# 1-Schematic_NRF24L01P-R.net
KiCad netlist of a schematic drawn in EasyEDA
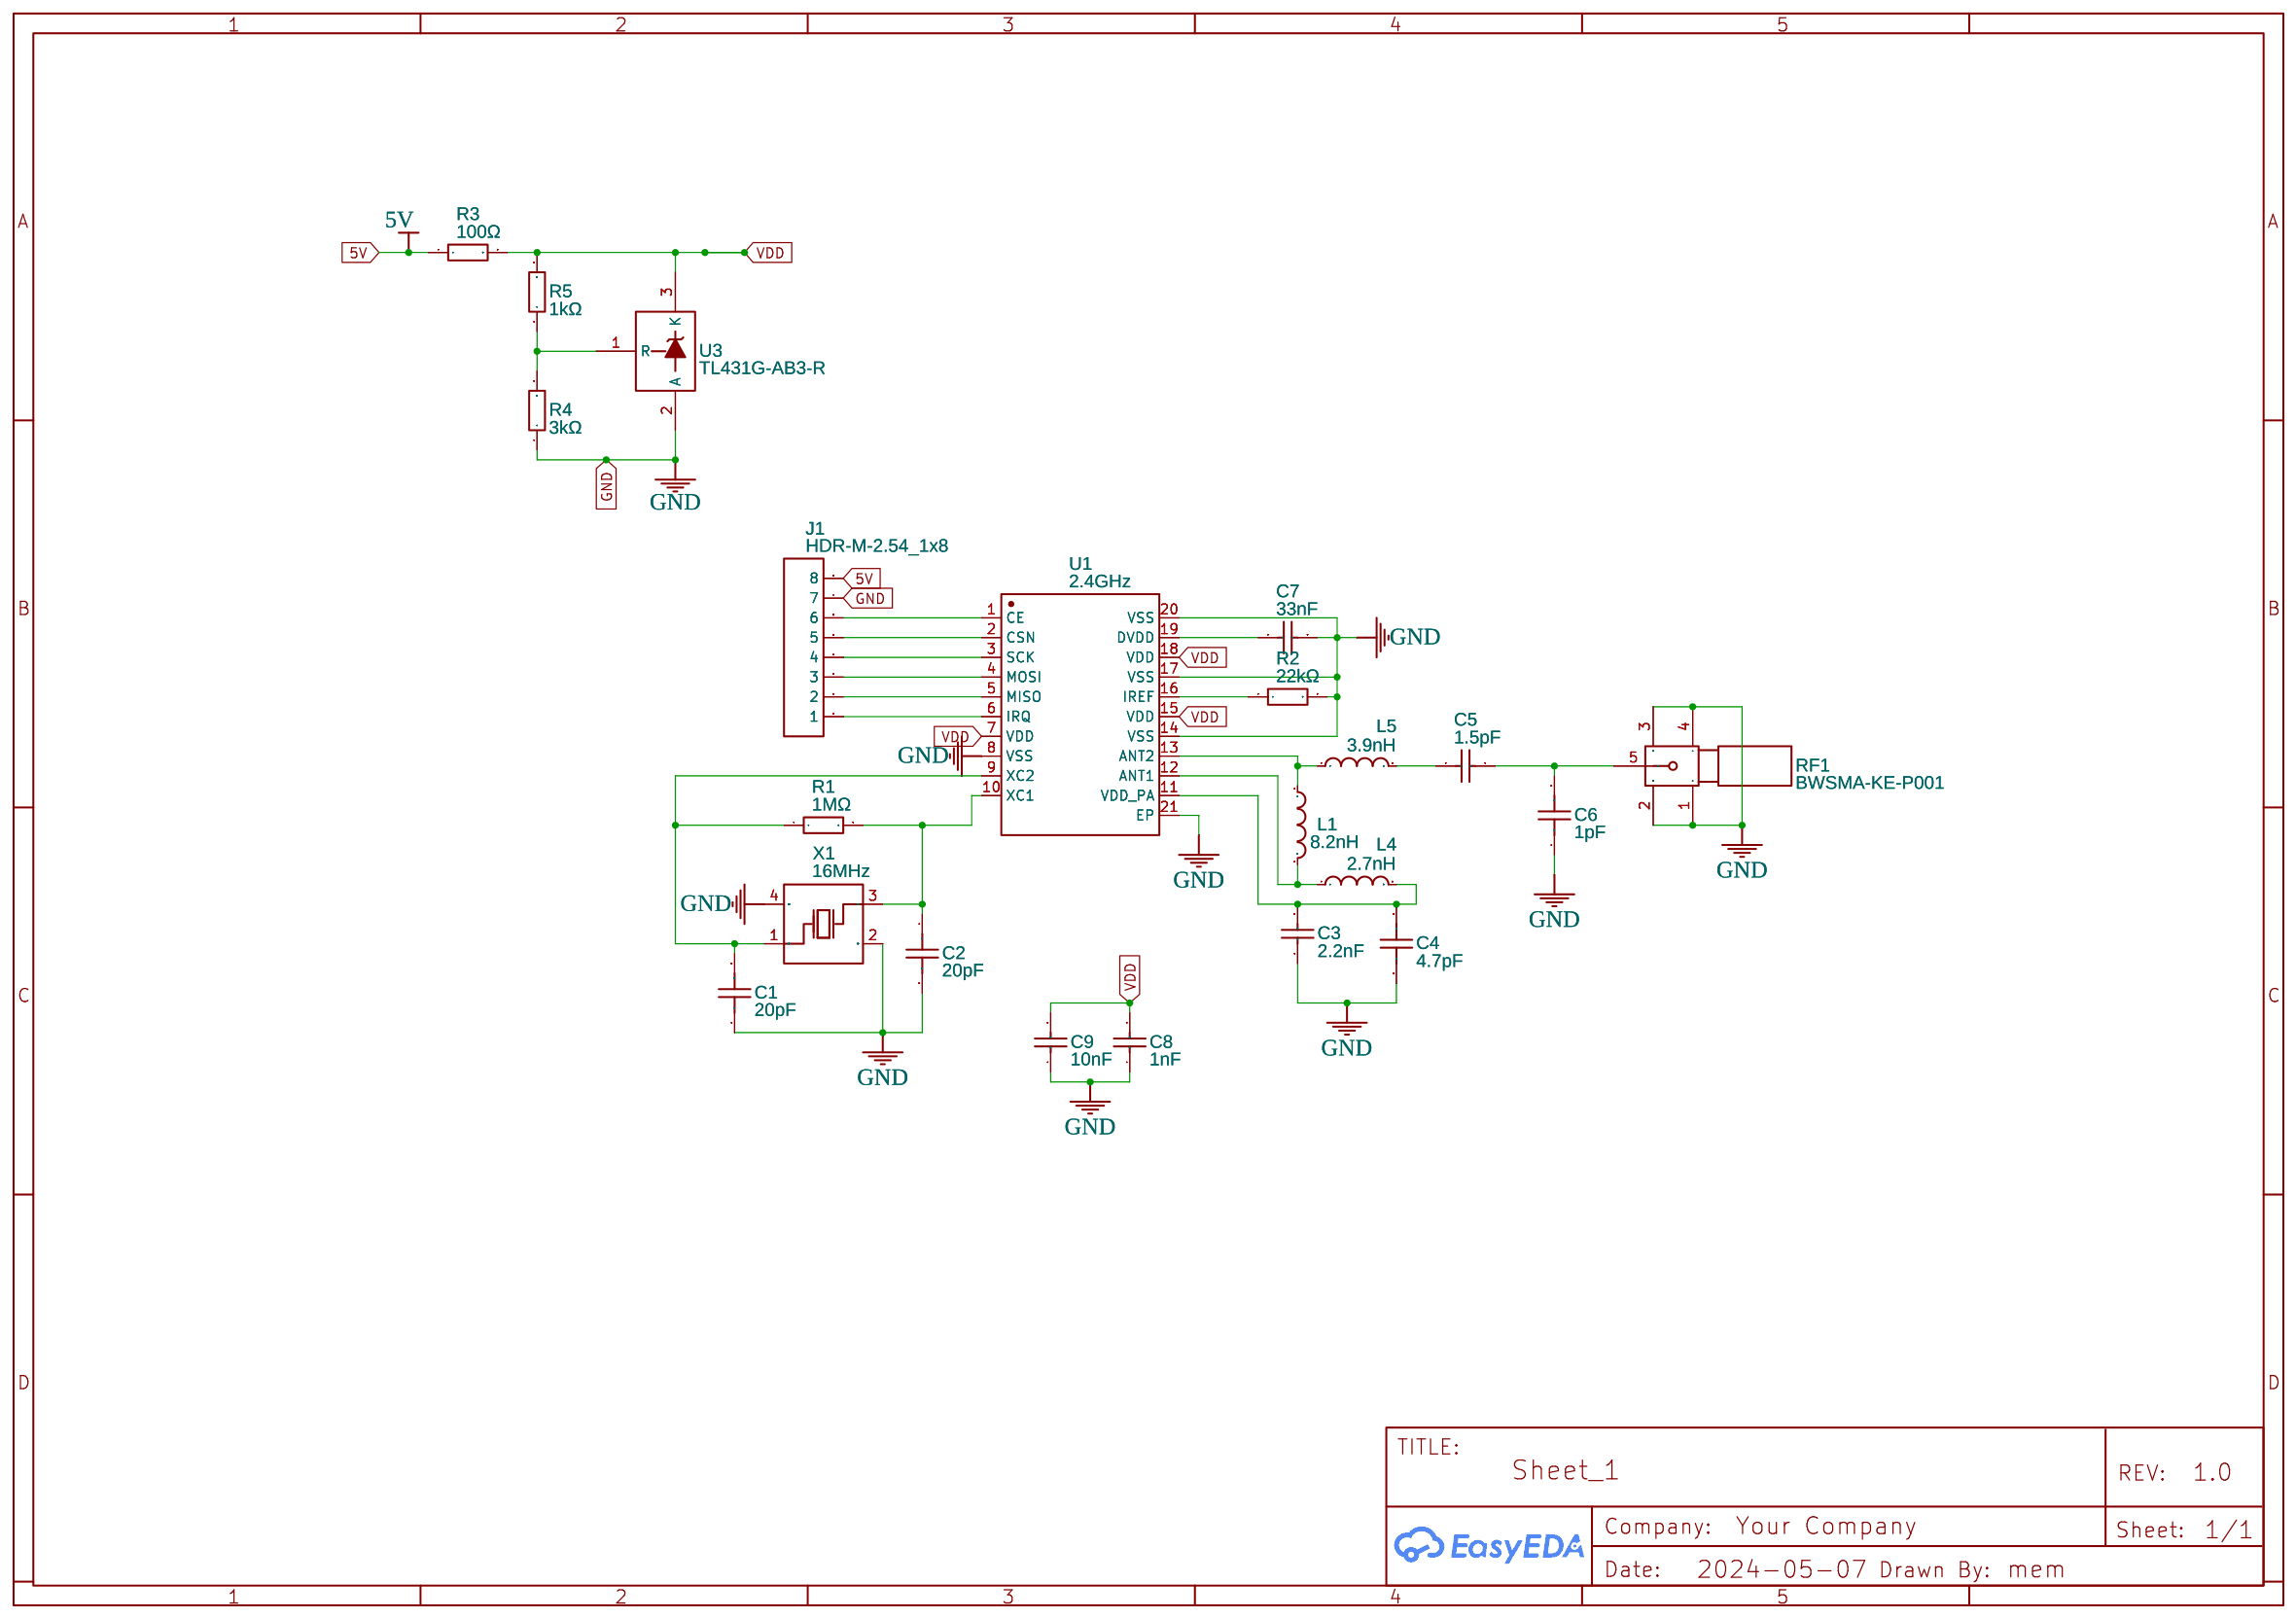
[diagram p0: schematic sheet]

(export (version "E")
  (design (tool "Eeschema 10.0.6"))
  (components
    (comp (ref "C1")
      (value "20pF")
      (fields
        (field (name "Manufacturer Part") "CC0805GRNPO9BN200")
        (field (name "Manufacturer") "YAGEO(国巨)")
      )
      (libsource (lib "") (part "CC0805GRNPO9BN200_1"))
    )
    (comp (ref "C2")
      (value "20pF")
      (fields
        (field (name "Manufacturer Part") "CC0805GRNPO9BN200")
        (field (name "Manufacturer") "YAGEO(国巨)")
      )
      (libsource (lib "") (part "CC0805GRNPO9BN200"))
    )
    (comp (ref "C3")
      (value "2.2nF")
      (fields (field (name "Manufacturer Part") "0805B222K500NT") (field (name "Manufacturer") "FH(风华)"))
      (libsource (lib "") (part "0805B222K500NT"))
    )
    (comp (ref "C4")
      (value "4.7pF")
      (fields
        (field (name "Manufacturer Part") "CC0805BRNPO9BN4R7")
        (field (name "Manufacturer") "YAGEO(国巨)")
      )
      (libsource (lib "") (part "CC0805BRNPO9BN4R7"))
    )
    (comp (ref "C5")
      (value "1.5pF")
      (fields (field (name "Manufacturer Part") "0603CG1R5C500NT") (field (name "Manufacturer") "FH(风华)"))
      (libsource (lib "") (part "0603CG1R5C500NT"))
    )
    (comp (ref "C6")
      (value "1pF")
      (fields
        (field (name "Manufacturer Part") "CC0805BRNPO9BN1R0")
        (field (name "Manufacturer") "YAGEO(国巨)")
      )
      (libsource (lib "") (part "CC0805BRNPO9BN1R0"))
    )
    (comp (ref "C7")
      (value "33nF")
      (fields
        (field (name "Manufacturer Part") "CC0805KRX7R9BB333")
        (field (name "Manufacturer") "YAGEO(国巨)")
      )
      (libsource (lib "") (part "CC0805KRX7R9BB333"))
    )
    (comp (ref "C8")
      (value "1nF")
      (fields (field (name "Manufacturer Part") "0805B102K500NT") (field (name "Manufacturer") "FH(风华)"))
      (libsource (lib "") (part "0805B102K500NT"))
    )
    (comp (ref "C9")
      (value "10nF")
      (fields (field (name "Manufacturer Part") "0805B103K500NT") (field (name "Manufacturer") "FH(风华)"))
      (libsource (lib "") (part "0805B103K500NT"))
    )
    (comp (ref "J1") (value "HDR-M-2.54_1x8") (libsource (lib "") (part "HDR-M-2.54_1x8")))
    (comp (ref "L1")
      (value "8.2nH")
      (fields (field (name "Manufacturer Part") "VHF201209H8N2J") (field (name "Manufacturer") "FH(风华)"))
      (libsource (lib "") (part "VHF201209H8N2J"))
    )
    (comp (ref "L4")
      (value "2.7nH")
      (fields
        (field (name "Manufacturer Part") "SCHF201209H2N7ST")
        (field (name "Manufacturer") "Yanchuang(研创)")
      )
      (libsource (lib "") (part "SCHF201209H2N7ST"))
    )
    (comp (ref "L5")
      (value "3.9nH")
      (fields
        (field (name "Manufacturer Part") "SCHF201209H3N9ST")
        (field (name "Manufacturer") "Yanchuang(研创)")
      )
      (libsource (lib "") (part "SCHF201209H3N9ST"))
    )
    (comp (ref "R1")
      (value "1MΩ")
      (fields
        (field (name "Manufacturer Part") "0805W8F1004T5E")
        (field (name "Manufacturer") "UNI-ROYAL(厚声)")
      )
      (libsource (lib "") (part "0805W8F1004T5E"))
    )
    (comp (ref "R2")
      (value "22kΩ")
      (fields
        (field (name "Manufacturer Part") "0805W8F2202T5E")
        (field (name "Manufacturer") "UNI-ROYAL(厚声)")
      )
      (libsource (lib "") (part "0805W8F2202T5E"))
    )
    (comp (ref "R3")
      (value "100Ω")
      (fields
        (field (name "Manufacturer Part") "1206W4F1000T5E")
        (field (name "Manufacturer") "UNI-ROYAL(厚声)")
      )
      (libsource (lib "") (part "1206W4F1000T5E"))
    )
    (comp (ref "R4")
      (value "3kΩ")
      (fields
        (field (name "Manufacturer Part") "1206W4F3001T5E")
        (field (name "Manufacturer") "UNI-ROYAL(厚声)")
      )
      (libsource (lib "") (part "1206W4F3001T5E"))
    )
    (comp (ref "R5")
      (value "1kΩ")
      (fields
        (field (name "Manufacturer Part") "1206W4F1001T5E")
        (field (name "Manufacturer") "UNI-ROYAL(厚声)")
      )
      (libsource (lib "") (part "1206W4F1001T5E"))
    )
    (comp (ref "RF1")
      (value "BWSMA-KE-P001")
      (fields (field (name "Manufacturer") "BAT WIRELESS(蝙蝠无线)"))
      (libsource (lib "") (part "BWSMA-KE-P001"))
    )
    (comp (ref "U1")
      (value "2.4GHz")
      (fields (field (name "Manufacturer Part") "NRF24L01P-R") (field (name "Manufacturer") "NORDIC"))
      (libsource (lib "") (part "NRF24L01P-R"))
    )
    (comp (ref "U3")
      (value "TL431G-AB3-R")
      (fields (field (name "Manufacturer") "UTC(友顺)"))
      (libsource (lib "") (part "TL431G-AB3-R"))
    )
    (comp (ref "X1")
      (value "16MHz")
      (fields (field (name "Manufacturer Part") "X322516MLB4SI") (field (name "Manufacturer") "YXC(扬兴晶振)"))
      (libsource (lib "") (part "X322516MLB4SI"))
    )
  )
  (nets
    (net (code "1") (name "5V") (class "Default")
      (node (ref "J1") (pin "8") (pinfunction "8_8") (pintype "unspecified"))
      (node (ref "R3") (pin "1") (pinfunction "1_1") (pintype "input"))
    )
    (net (code "2") (name "GND") (class "Default")
      (node (ref "C1") (pin "1") (pinfunction "1_1") (pintype "unspecified"))
      (node (ref "C2") (pin "2") (pinfunction "2_2") (pintype "unspecified"))
      (node (ref "C3") (pin "1") (pinfunction "1_1") (pintype "input"))
      (node (ref "C4") (pin "1") (pinfunction "1_1") (pintype "unspecified"))
      (node (ref "C6") (pin "1") (pinfunction "1_1") (pintype "unspecified"))
      (node (ref "C7") (pin "2") (pinfunction "2_2") (pintype "input"))
      (node (ref "C8") (pin "1") (pinfunction "1_1") (pintype "input"))
      (node (ref "C9") (pin "1") (pinfunction "1_1") (pintype "input"))
      (node (ref "J1") (pin "7") (pinfunction "7_7") (pintype "unspecified"))
      (node (ref "R2") (pin "2") (pinfunction "2_2") (pintype "input"))
      (node (ref "R4") (pin "1") (pinfunction "1_1") (pintype "input"))
      (node (ref "RF1") (pin "1") (pinfunction "1_1") (pintype "unspecified"))
      (node (ref "RF1") (pin "2") (pinfunction "2_2") (pintype "unspecified"))
      (node (ref "RF1") (pin "3") (pinfunction "3_3") (pintype "unspecified"))
      (node (ref "RF1") (pin "4") (pinfunction "4_4") (pintype "unspecified"))
      (node (ref "U1") (pin "14") (pinfunction "VSS_14") (pintype "unspecified"))
      (node (ref "U1") (pin "17") (pinfunction "VSS_17") (pintype "unspecified"))
      (node (ref "U1") (pin "20") (pinfunction "VSS_20") (pintype "unspecified"))
      (node (ref "U1") (pin "21") (pinfunction "EP_21") (pintype "unspecified"))
      (node (ref "U1") (pin "8") (pinfunction "VSS_8") (pintype "unspecified"))
      (node (ref "U3") (pin "2") (pinfunction "A_2") (pintype "unspecified"))
      (node (ref "X1") (pin "2") (pinfunction "GND_2") (pintype "unspecified"))
      (node (ref "X1") (pin "4") (pinfunction "GND_4") (pintype "unspecified"))
    )
    (net (code "3") (name "Net-(C5-Pad1)") (class "Default")
      (node (ref "C5") (pin "1") (pinfunction "1_1") (pintype "input"))
      (node (ref "L5") (pin "2") (pinfunction "2_2") (pintype "unspecified"))
    )
    (net (code "4") (name "Net-(C5-Pad2)") (class "Default")
      (node (ref "C5") (pin "2") (pinfunction "2_2") (pintype "input"))
      (node (ref "C6") (pin "2") (pinfunction "2_2") (pintype "unspecified"))
      (node (ref "RF1") (pin "5") (pinfunction "5_5") (pintype "unspecified"))
    )
    (net (code "5") (name "Net-(U1-ANT1)") (class "Default")
      (node (ref "L1") (pin "2") (pinfunction "2_2") (pintype "unspecified"))
      (node (ref "L4") (pin "1") (pinfunction "1_1") (pintype "unspecified"))
      (node (ref "U1") (pin "12") (pinfunction "ANT1_12") (pintype "unspecified"))
    )
    (net (code "6") (name "Net-(U1-ANT2)") (class "Default")
      (node (ref "L1") (pin "1") (pinfunction "1_1") (pintype "unspecified"))
      (node (ref "L5") (pin "1") (pinfunction "1_1") (pintype "unspecified"))
      (node (ref "U1") (pin "13") (pinfunction "ANT2_13") (pintype "unspecified"))
    )
    (net (code "7") (name "Net-(U1-CE)") (class "Default")
      (node (ref "J1") (pin "6") (pinfunction "6_6") (pintype "unspecified"))
      (node (ref "U1") (pin "1") (pinfunction "CE_1") (pintype "unspecified"))
    )
    (net (code "8") (name "Net-(U1-CSN)") (class "Default")
      (node (ref "J1") (pin "5") (pinfunction "5_5") (pintype "unspecified"))
      (node (ref "U1") (pin "2") (pinfunction "CSN_2") (pintype "unspecified"))
    )
    (net (code "9") (name "Net-(U1-DVDD)") (class "Default")
      (node (ref "C7") (pin "1") (pinfunction "1_1") (pintype "input"))
      (node (ref "U1") (pin "19") (pinfunction "DVDD_19") (pintype "unspecified"))
    )
    (net (code "10") (name "Net-(U1-IREF)") (class "Default")
      (node (ref "R2") (pin "1") (pinfunction "1_1") (pintype "input"))
      (node (ref "U1") (pin "16") (pinfunction "IREF_16") (pintype "unspecified"))
    )
    (net (code "11") (name "Net-(U1-IRQ)") (class "Default")
      (node (ref "J1") (pin "1") (pinfunction "1_1") (pintype "unspecified"))
      (node (ref "U1") (pin "6") (pinfunction "IRQ_6") (pintype "unspecified"))
    )
    (net (code "12") (name "Net-(U1-MISO)") (class "Default")
      (node (ref "J1") (pin "2") (pinfunction "2_2") (pintype "unspecified"))
      (node (ref "U1") (pin "5") (pinfunction "MISO_5") (pintype "unspecified"))
    )
    (net (code "13") (name "Net-(U1-MOSI)") (class "Default")
      (node (ref "J1") (pin "3") (pinfunction "3_3") (pintype "unspecified"))
      (node (ref "U1") (pin "4") (pinfunction "MOSI_4") (pintype "unspecified"))
    )
    (net (code "14") (name "Net-(U1-SCK)") (class "Default")
      (node (ref "J1") (pin "4") (pinfunction "4_4") (pintype "unspecified"))
      (node (ref "U1") (pin "3") (pinfunction "SCK_3") (pintype "unspecified"))
    )
    (net (code "15") (name "Net-(U1-VDD_PA)") (class "Default")
      (node (ref "C3") (pin "2") (pinfunction "2_2") (pintype "input"))
      (node (ref "C4") (pin "2") (pinfunction "2_2") (pintype "unspecified"))
      (node (ref "L4") (pin "2") (pinfunction "2_2") (pintype "unspecified"))
      (node (ref "U1") (pin "11") (pinfunction "VDD_PA_11") (pintype "unspecified"))
    )
    (net (code "16") (name "Net-(U1-XC1)") (class "Default")
      (node (ref "C2") (pin "1") (pinfunction "1_1") (pintype "unspecified"))
      (node (ref "R1") (pin "2") (pinfunction "2_2") (pintype "input"))
      (node (ref "U1") (pin "10") (pinfunction "XC1_10") (pintype "unspecified"))
      (node (ref "X1") (pin "3") (pinfunction "OSC2_3") (pintype "unspecified"))
    )
    (net (code "17") (name "Net-(U1-XC2)") (class "Default")
      (node (ref "C1") (pin "2") (pinfunction "2_2") (pintype "unspecified"))
      (node (ref "R1") (pin "1") (pinfunction "1_1") (pintype "input"))
      (node (ref "U1") (pin "9") (pinfunction "XC2_9") (pintype "unspecified"))
      (node (ref "X1") (pin "1") (pinfunction "OSC1_1") (pintype "unspecified"))
    )
    (net (code "18") (name "Net-(U3-R)") (class "Default")
      (node (ref "R4") (pin "2") (pinfunction "2_2") (pintype "input"))
      (node (ref "R5") (pin "1") (pinfunction "1_1") (pintype "input"))
      (node (ref "U3") (pin "1") (pinfunction "R_1") (pintype "unspecified"))
    )
    (net (code "19") (name "VDD") (class "Default")
      (node (ref "C8") (pin "2") (pinfunction "2_2") (pintype "input"))
      (node (ref "C9") (pin "2") (pinfunction "2_2") (pintype "input"))
      (node (ref "R3") (pin "2") (pinfunction "2_2") (pintype "input"))
      (node (ref "R5") (pin "2") (pinfunction "2_2") (pintype "input"))
      (node (ref "U1") (pin "15") (pinfunction "VDD_15") (pintype "unspecified"))
      (node (ref "U1") (pin "18") (pinfunction "VDD_18") (pintype "unspecified"))
      (node (ref "U1") (pin "7") (pinfunction "VDD_7") (pintype "unspecified"))
      (node (ref "U3") (pin "3") (pinfunction "K_3") (pintype "unspecified"))
    )
  )
)
